# OTHERS.net
KiCad netlist of a schematic drawn in Altium Designer
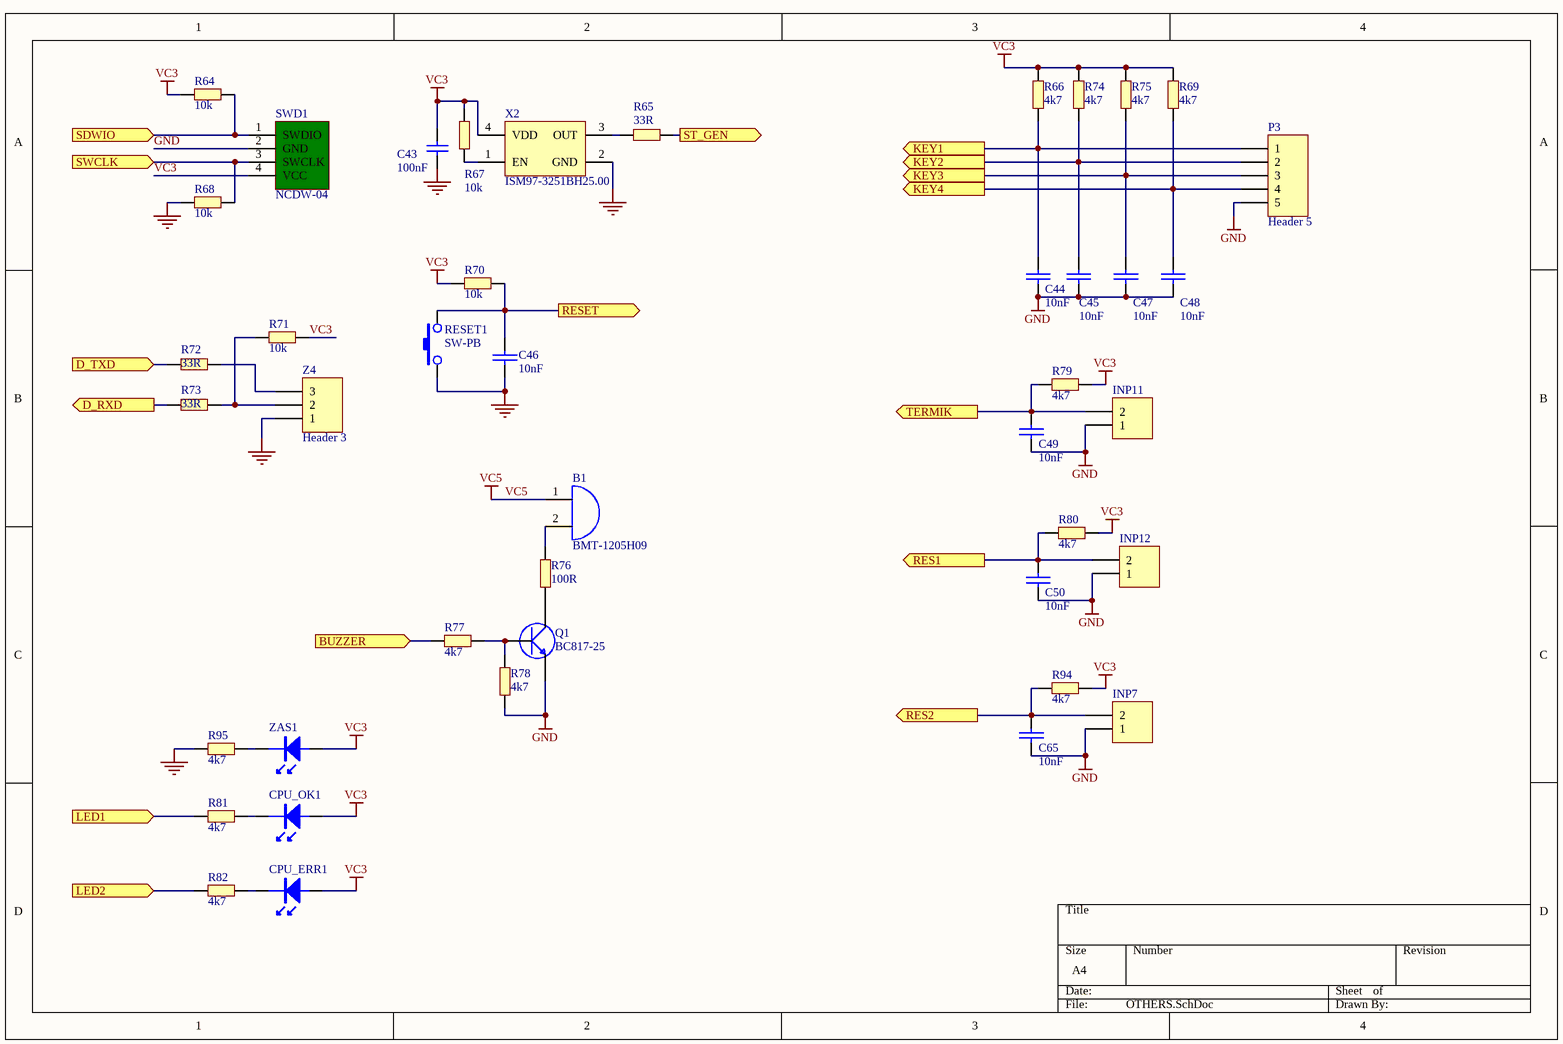
[diagram p0: OTHERS.SchDoc]

(export (version "E")
  (design (tool "Eeschema 10.0.6"))
  (components
    (comp (ref "B1") (value "BMT-1205H09") (footprint "BMT-1205H09") (libsource (lib "*") (part "BUZZER")))
    (comp (ref "C43")
      (value "100nF")
      (footprint "0603C")
      (description "Capacitor,100nF,16V,X7R,10%,0402,YAGEO")
      (libsource (lib "MCD_TOOLS") (part "Cap_100nF_X7R_10%_0402"))
    )
    (comp (ref "C44")
      (value "10nF")
      (footprint "0603C")
      (description "Capacitor")
      (libsource (lib "*") (part "CAP"))
    )
    (comp (ref "C45")
      (value "10nF")
      (footprint "0603C")
      (description "Capacitor")
      (libsource (lib "*") (part "CAP"))
    )
    (comp (ref "C46")
      (value "10nF")
      (footprint "0603C")
      (description "Capacitor")
      (libsource (lib "*") (part "CAP"))
    )
    (comp (ref "C47")
      (value "10nF")
      (footprint "0603C")
      (description "Capacitor")
      (libsource (lib "*") (part "CAP"))
    )
    (comp (ref "C48")
      (value "10nF")
      (footprint "0603C")
      (description "Capacitor")
      (libsource (lib "*") (part "CAP"))
    )
    (comp (ref "C49")
      (value "10nF")
      (footprint "0603C")
      (description "Capacitor")
      (libsource (lib "*") (part "CAP"))
    )
    (comp (ref "C50")
      (value "10nF")
      (footprint "0603C")
      (description "Capacitor")
      (libsource (lib "*") (part "CAP"))
    )
    (comp (ref "C65")
      (value "10nF")
      (footprint "0603C")
      (description "Capacitor")
      (libsource (lib "*") (part "CAP"))
    )
    (comp (ref "CPU_ERR1") (value "LED0805") (footprint "0603DR") (libsource (lib "*") (part "LED1206")))
    (comp (ref "CPU_OK1") (value "green") (footprint "0603DG") (libsource (lib "*") (part "LED1206")))
    (comp (ref "INP7")
      (value "Header 2")
      (footprint "JST-XH-2Y-2.54")
      (description "Header, 2-Pin")
      (fields (field (name "PUBLISHER") "Altium Limited"))
      (libsource (lib "Miscellaneous Connectors") (part "Header 2"))
    )
    (comp (ref "INP11")
      (value "Header 2")
      (footprint "JST-XH-2Y-2.54")
      (description "Header, 2-Pin")
      (fields (field (name "PUBLISHER") "Altium Limited"))
      (libsource (lib "Miscellaneous Connectors") (part "Header 2"))
    )
    (comp (ref "INP12")
      (value "Header 2")
      (footprint "JST-XH-2Y-2.54")
      (description "Header, 2-Pin")
      (fields (field (name "PUBLISHER") "Altium Limited"))
      (libsource (lib "Miscellaneous Connectors") (part "Header 2"))
    )
    (comp (ref "P3")
      (value "Header 5")
      (footprint "JST-B5B-XH-A")
      (description "Header, 5-Pin")
      (fields (field (name "PUBLISHER") "Altium Limited"))
      (libsource (lib "Miscellaneous Connectors") (part "Header 5"))
    )
    (comp (ref "Q1") (value "BC817-25") (footprint "SOT23-3Q") (libsource (lib "*") (part "S9013SMD")))
    (comp (ref "R64") (value "10k") (footprint "0603R") (libsource (lib "*") (part "RES3")))
    (comp (ref "R65") (value "33R") (footprint "0603R") (libsource (lib "*") (part "RES3")))
    (comp (ref "R66") (value "4k7") (footprint "0603R") (libsource (lib "") (part "RES3_1")))
    (comp (ref "R67") (value "10k") (footprint "0603R") (libsource (lib "") (part "RES3_2")))
    (comp (ref "R68") (value "10k") (footprint "0603R") (libsource (lib "*") (part "RES3")))
    (comp (ref "R69") (value "4k7") (footprint "0603R") (libsource (lib "") (part "RES3_1")))
    (comp (ref "R70") (value "10k") (footprint "0603R") (libsource (lib "*") (part "RES3")))
    (comp (ref "R71") (value "10k") (footprint "0603R") (libsource (lib "*") (part "RES3")))
    (comp (ref "R72") (value "33R") (footprint "0603R") (libsource (lib "") (part "RES3_3")))
    (comp (ref "R73") (value "33R") (footprint "0603R") (libsource (lib "") (part "RES3_3")))
    (comp (ref "R74") (value "4k7") (footprint "0603R") (libsource (lib "") (part "RES3_1")))
    (comp (ref "R75") (value "4k7") (footprint "0603R") (libsource (lib "") (part "RES3_1")))
    (comp (ref "R76") (value "100R") (footprint "0603R") (libsource (lib "") (part "RES3_2")))
    (comp (ref "R77") (value "4k7") (footprint "0603R") (libsource (lib "") (part "RES3_3")))
    (comp (ref "R78") (value "4k7") (footprint "0603R") (libsource (lib "") (part "RES3_2")))
    (comp (ref "R79") (value "4k7") (footprint "0603R") (libsource (lib "*") (part "RES3")))
    (comp (ref "R80") (value "4k7") (footprint "0603R") (libsource (lib "*") (part "RES3")))
    (comp (ref "R81") (value "4k7") (footprint "0603R") (libsource (lib "") (part "RES3_3")))
    (comp (ref "R82") (value "4k7") (footprint "0603R") (libsource (lib "") (part "RES3_3")))
    (comp (ref "R94") (value "4k7") (footprint "0603R") (libsource (lib "*") (part "RES3")))
    (comp (ref "R95") (value "4k7") (footprint "0603R") (libsource (lib "") (part "RES3_3")))
    (comp (ref "RESET1") (value "SW-PB") (footprint "DTSM31N_2") (libsource (lib "*") (part "SW-PB")))
    (comp (ref "SWD1")
      (value "NCDW-04")
      (footprint "PIN4")
      (description "Header, 4-Pin")
      (fields (field (name "PUBLISHER") "Altium Limited"))
      (libsource (lib "GkSchlib") (part "SW_CON"))
    )
    (comp (ref "X2")
      (value "ISM97-3251BH25.00")
      (footprint "GEN_SMD1_1")
      (description "Oscillator 25.00Mhz, -+50PPM, 3.3V, Temp -55 to +125°C")
      (libsource (lib "MCD_TOOLS") (part "OSC_25M_NZ2520SB"))
    )
    (comp (ref "Z4")
      (value "Header 3")
      (footprint "PIN3")
      (description "Header, 3-Pin")
      (fields (field (name "PUBLISHER") "Altium Limited"))
      (libsource (lib "Miscellaneous Connectors") (part "Header 3"))
    )
    (comp (ref "ZAS1") (value "green") (footprint "0603DG") (libsource (lib "*") (part "LED1206")))
  )
  (nets
    (net (code "1") (name "/BUZZER") (class "Default") (node (ref "R77") (pin "2") (pintype "passive")))
    (net (code "2") (name "/D_RXD") (class "Default") (node (ref "R73") (pin "2") (pintype "passive")))
    (net (code "3") (name "/D_TXD") (class "Default") (node (ref "R72") (pin "2") (pintype "passive")))
    (net (code "4") (name "/KEY1") (class "Default")
      (node (ref "C44") (pin "1") (pinfunction "1_1") (pintype "passive"))
      (node (ref "P3") (pin "1") (pinfunction "1_1") (pintype "passive"))
      (node (ref "R66") (pin "1") (pintype "passive"))
    )
    (net (code "5") (name "/KEY2") (class "Default")
      (node (ref "C45") (pin "1") (pinfunction "1_1") (pintype "passive"))
      (node (ref "P3") (pin "2") (pinfunction "2_2") (pintype "passive"))
      (node (ref "R74") (pin "1") (pintype "passive"))
    )
    (net (code "6") (name "/KEY3") (class "Default")
      (node (ref "C47") (pin "1") (pinfunction "1_1") (pintype "passive"))
      (node (ref "P3") (pin "3") (pinfunction "3_3") (pintype "passive"))
      (node (ref "R75") (pin "1") (pintype "passive"))
    )
    (net (code "7") (name "/KEY4") (class "Default")
      (node (ref "C48") (pin "1") (pinfunction "1_1") (pintype "passive"))
      (node (ref "P3") (pin "4") (pinfunction "4_4") (pintype "passive"))
      (node (ref "R69") (pin "1") (pintype "passive"))
    )
    (net (code "8") (name "/LED1") (class "Default") (node (ref "R81") (pin "2") (pintype "passive")))
    (net (code "9") (name "/LED2") (class "Default") (node (ref "R82") (pin "2") (pintype "passive")))
    (net (code "10") (name "/RES1") (class "Default")
      (node (ref "C50") (pin "1") (pinfunction "1_1") (pintype "passive"))
      (node (ref "INP12") (pin "2") (pinfunction "2_2") (pintype "passive"))
      (node (ref "R80") (pin "1") (pintype "passive"))
    )
    (net (code "11") (name "/RES2") (class "Default")
      (node (ref "C65") (pin "1") (pinfunction "1_1") (pintype "passive"))
      (node (ref "INP7") (pin "2") (pinfunction "2_2") (pintype "passive"))
      (node (ref "R94") (pin "1") (pintype "passive"))
    )
    (net (code "12") (name "/RESET") (class "Default")
      (node (ref "C46") (pin "1") (pinfunction "1_1") (pintype "passive"))
      (node (ref "R70") (pin "2") (pintype "passive"))
      (node (ref "RESET1") (pin "2") (pinfunction "2_2") (pintype "passive"))
    )
    (net (code "13") (name "/SDWIO") (class "Default")
      (node (ref "R64") (pin "2") (pintype "passive"))
      (node (ref "SWD1") (pin "1") (pinfunction "SWDIO_1") (pintype "passive"))
    )
    (net (code "14") (name "/ST_GEN") (class "Default") (node (ref "R65") (pin "2") (pintype "passive")))
    (net (code "15") (name "/SWCLK") (class "Default")
      (node (ref "R68") (pin "2") (pintype "passive"))
      (node (ref "SWD1") (pin "3") (pinfunction "SWCLK_3") (pintype "passive"))
    )
    (net (code "16") (name "/TERMIK") (class "Default")
      (node (ref "C49") (pin "1") (pinfunction "1_1") (pintype "passive"))
      (node (ref "INP11") (pin "2") (pinfunction "2_2") (pintype "passive"))
      (node (ref "R79") (pin "1") (pintype "passive"))
    )
    (net (code "17") (name "GND") (class "Default")
      (node (ref "C43") (pin "1") (pinfunction "1_1") (pintype "passive"))
      (node (ref "C44") (pin "2") (pinfunction "2_2") (pintype "passive"))
      (node (ref "C45") (pin "2") (pinfunction "2_2") (pintype "passive"))
      (node (ref "C46") (pin "2") (pinfunction "2_2") (pintype "passive"))
      (node (ref "C47") (pin "2") (pinfunction "2_2") (pintype "passive"))
      (node (ref "C48") (pin "2") (pinfunction "2_2") (pintype "passive"))
      (node (ref "C49") (pin "2") (pinfunction "2_2") (pintype "passive"))
      (node (ref "C50") (pin "2") (pinfunction "2_2") (pintype "passive"))
      (node (ref "C65") (pin "2") (pinfunction "2_2") (pintype "passive"))
      (node (ref "INP11") (pin "1") (pinfunction "1_1") (pintype "passive"))
      (node (ref "INP12") (pin "1") (pinfunction "1_1") (pintype "passive"))
      (node (ref "INP7") (pin "1") (pinfunction "1_1") (pintype "passive"))
      (node (ref "P3") (pin "5") (pinfunction "5_5") (pintype "passive"))
      (node (ref "Q1") (pin "E") (pinfunction "E_E") (pintype "passive"))
      (node (ref "R68") (pin "1") (pintype "passive"))
      (node (ref "R78") (pin "2") (pintype "passive"))
      (node (ref "R95") (pin "2") (pintype "passive"))
      (node (ref "RESET1") (pin "1") (pinfunction "1_1") (pintype "passive"))
      (node (ref "SWD1") (pin "2") (pinfunction "GND_2") (pintype "passive"))
      (node (ref "X2") (pin "2") (pinfunction "GND_2") (pintype "passive"))
      (node (ref "Z4") (pin "1") (pinfunction "1_1") (pintype "passive"))
    )
    (net (code "18") (name "Net-(B1-Pad2)") (class "Default")
      (node (ref "B1") (pin "2") (pinfunction "2_2") (pintype "passive"))
      (node (ref "R76") (pin "1") (pintype "passive"))
    )
    (net (code "19") (name "Net-(CPU_ERR1-PadK)") (class "Default")
      (node (ref "CPU_ERR1") (pin "K") (pinfunction "K_K") (pintype "passive"))
      (node (ref "R82") (pin "1") (pintype "passive"))
    )
    (net (code "20") (name "Net-(CPU_OK1-PadK)") (class "Default")
      (node (ref "CPU_OK1") (pin "K") (pinfunction "K_K") (pintype "passive"))
      (node (ref "R81") (pin "1") (pintype "passive"))
    )
    (net (code "21") (name "Net-(Q1-PadB)") (class "Default")
      (node (ref "Q1") (pin "B") (pinfunction "B_B") (pintype "passive"))
      (node (ref "R77") (pin "1") (pintype "passive"))
      (node (ref "R78") (pin "1") (pintype "passive"))
    )
    (net (code "22") (name "Net-(Q1-PadC)") (class "Default")
      (node (ref "Q1") (pin "C") (pinfunction "C_C") (pintype "passive"))
      (node (ref "R76") (pin "2") (pintype "passive"))
    )
    (net (code "23") (name "Net-(R71-Pad1)") (class "Default")
      (node (ref "R71") (pin "1") (pintype "passive"))
      (node (ref "R73") (pin "1") (pintype "passive"))
      (node (ref "Z4") (pin "2") (pinfunction "2_2") (pintype "passive"))
    )
    (net (code "24") (name "Net-(R72-Pad1)") (class "Default")
      (node (ref "R72") (pin "1") (pintype "passive"))
      (node (ref "Z4") (pin "3") (pinfunction "3_3") (pintype "passive"))
    )
    (net (code "25") (name "Net-(R95-Pad1)") (class "Default")
      (node (ref "R95") (pin "1") (pintype "passive"))
      (node (ref "ZAS1") (pin "K") (pinfunction "K_K") (pintype "passive"))
    )
    (net (code "26") (name "Net-(X2-EN)") (class "Default")
      (node (ref "R67") (pin "2") (pintype "passive"))
      (node (ref "X2") (pin "1") (pinfunction "EN_1") (pintype "passive"))
    )
    (net (code "27") (name "Net-(X2-OUT)") (class "Default")
      (node (ref "R65") (pin "1") (pintype "passive"))
      (node (ref "X2") (pin "3") (pinfunction "OUT_3") (pintype "passive"))
    )
    (net (code "28") (name "VC3") (class "Default")
      (node (ref "C43") (pin "2") (pinfunction "2_2") (pintype "passive"))
      (node (ref "CPU_ERR1") (pin "A") (pinfunction "A_A") (pintype "passive"))
      (node (ref "CPU_OK1") (pin "A") (pinfunction "A_A") (pintype "passive"))
      (node (ref "R64") (pin "1") (pintype "passive"))
      (node (ref "R66") (pin "2") (pintype "passive"))
      (node (ref "R67") (pin "1") (pintype "passive"))
      (node (ref "R69") (pin "2") (pintype "passive"))
      (node (ref "R70") (pin "1") (pintype "passive"))
      (node (ref "R71") (pin "2") (pintype "passive"))
      (node (ref "R74") (pin "2") (pintype "passive"))
      (node (ref "R75") (pin "2") (pintype "passive"))
      (node (ref "R79") (pin "2") (pintype "passive"))
      (node (ref "R80") (pin "2") (pintype "passive"))
      (node (ref "R94") (pin "2") (pintype "passive"))
      (node (ref "SWD1") (pin "4") (pinfunction "VCC_4") (pintype "passive"))
      (node (ref "X2") (pin "4") (pinfunction "VDD_4") (pintype "passive"))
      (node (ref "ZAS1") (pin "A") (pinfunction "A_A") (pintype "passive"))
    )
    (net (code "29") (name "VC5") (class "Default")
      (node (ref "B1") (pin "1") (pinfunction "1_1") (pintype "passive"))
    )
  )
)
